# MCU.net
KiCad netlist of a schematic drawn in Altium Designer
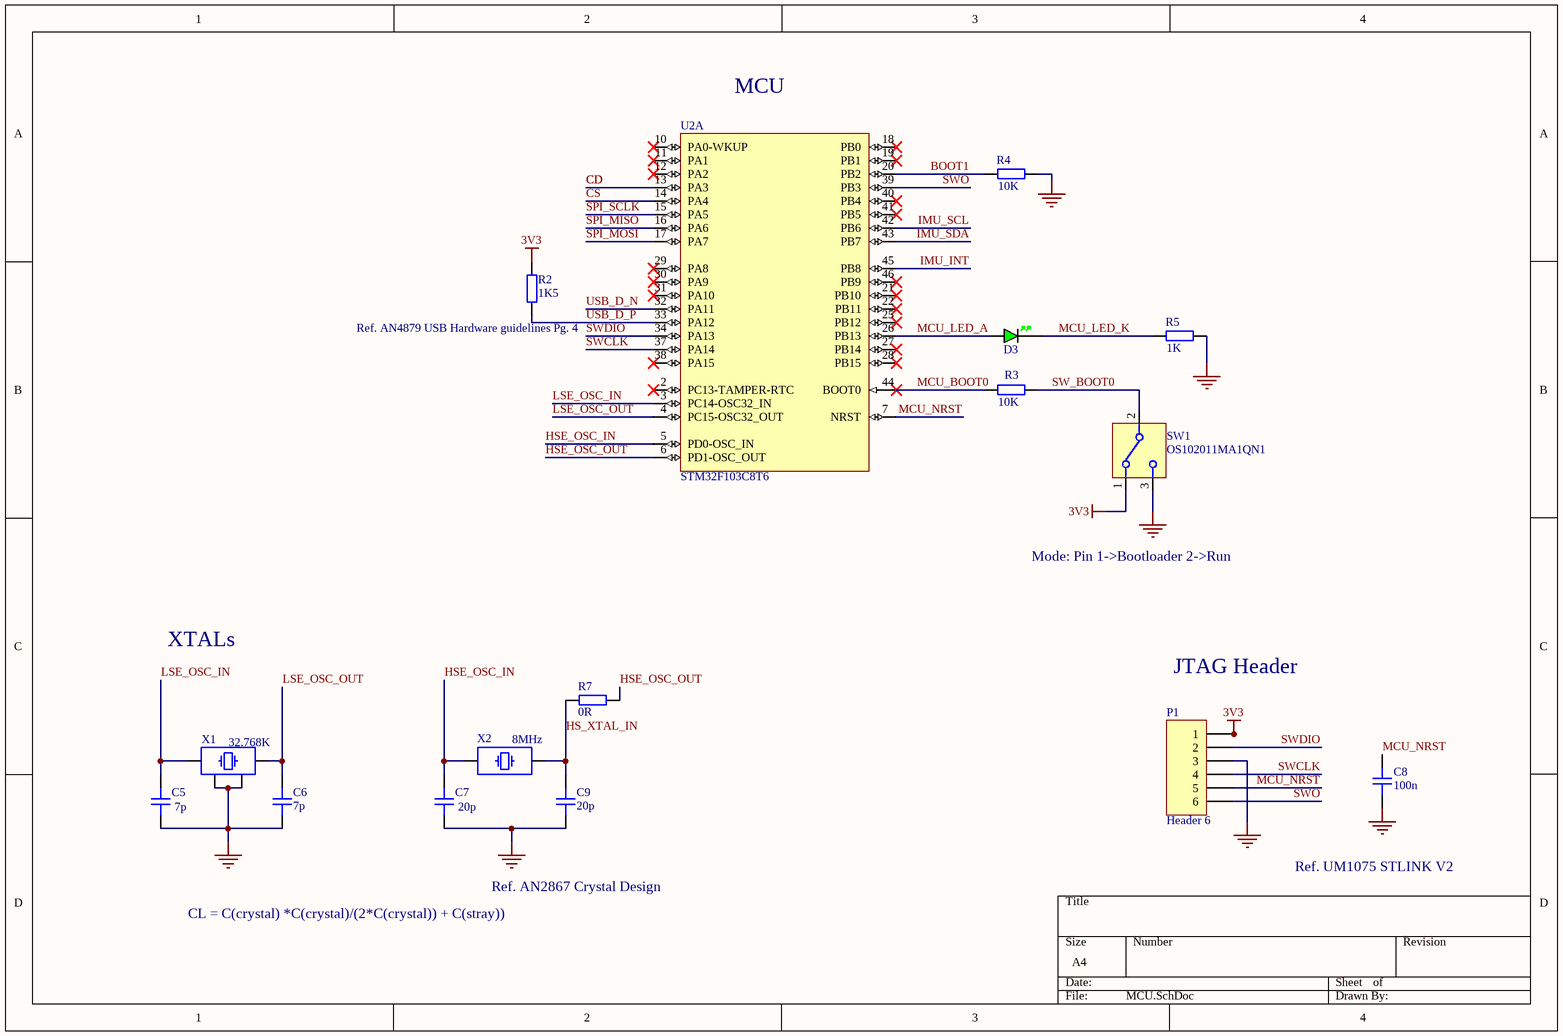
[diagram p0: MCU.SchDoc]

(export (version "E")
  (design (tool "Eeschema 10.0.6"))
  (components
    (comp (ref "C5")
      (value "7p")
      (footprint "CAP_0402")
      (description "Capacitor SMD 0402")
      (libsource (lib "Schematic-Lib-PhilsLab") (part "CAP_0402"))
    )
    (comp (ref "C6")
      (value "7p")
      (footprint "CAP_0402")
      (description "Capacitor SMD 0402")
      (libsource (lib "Schematic-Lib-PhilsLab") (part "CAP_0402"))
    )
    (comp (ref "C7")
      (value "20p")
      (footprint "CAP_0402")
      (description "Capacitor SMD 0402")
      (libsource (lib "Schematic-Lib-PhilsLab") (part "CAP_0402"))
    )
    (comp (ref "C8")
      (value "100n")
      (footprint "CAP_0402")
      (description "Capacitor SMD 0402")
      (libsource (lib "Schematic-Lib-PhilsLab") (part "CAP_0402"))
    )
    (comp (ref "C9")
      (value "20p")
      (footprint "CAP_0402")
      (description "Capacitor SMD 0402")
      (libsource (lib "Schematic-Lib-PhilsLab") (part "CAP_0402"))
    )
    (comp (ref "D3")
      (value "GREEN")
      (footprint "LED_0402_GREEN")
      (description "LED 0402 GREEN SMD")
      (libsource (lib "Schematic-Lib-PhilsLab") (part "LED_0402_GREEN"))
    )
    (comp (ref "P1")
      (value "Header 6")
      (footprint "HDR1X6")
      (description "Header, 6-Pin")
      (fields (field (name "PUBLISHER") "Altium Limited"))
      (libsource (lib "Miscellaneous Connectors") (part "Header 6"))
    )
    (comp (ref "R2")
      (value "1K5")
      (footprint "RES_0402")
      (description "Resistor SMD 0402")
      (libsource (lib "Schematic-Lib-PhilsLab") (part "RES_0402"))
    )
    (comp (ref "R3")
      (value "10K")
      (footprint "RES_0402")
      (description "Resistor SMD 0402")
      (libsource (lib "Schematic-Lib-PhilsLab") (part "RES_0402"))
    )
    (comp (ref "R4")
      (value "10K")
      (footprint "RES_0402")
      (description "Resistor SMD 0402")
      (libsource (lib "Schematic-Lib-PhilsLab") (part "RES_0402"))
    )
    (comp (ref "R5")
      (value "1K")
      (footprint "RES_0402")
      (description "Resistor SMD 0402")
      (libsource (lib "Schematic-Lib-PhilsLab") (part "RES_0402"))
    )
    (comp (ref "R7")
      (value "0R")
      (footprint "RES_0402")
      (description "Resistor SMD 0402")
      (libsource (lib "Schematic-Lib-PhilsLab") (part "RES_0402"))
    )
    (comp (ref "SW1")
      (value "OS102011MA1QN1")
      (footprint "OS102011MA1QN1")
      (description "Slide Switch SPDT Horizontal THT")
      (fields (field (name "MANUFACTURER") "C&K"))
      (libsource (lib "Schematic-Lib-PhilsLab") (part "OS102011MA1QN1"))
    )
    (comp (ref "U2")
      (value "STM32F103C8T6")
      (footprint "STM-LQFP48_L")
      (libsource (lib "Altium Content Vault") (part "MC-ARM-STM32F103X8_B-SQ48"))
    )
    (comp (ref "X1")
      (value "32.768K")
      (footprint "XTAL_2520")
      (description "Crystal SMD 2520")
      (libsource (lib "Schematic-Lib-PhilsLab") (part "XTAL_2520"))
    )
    (comp (ref "X2")
      (value "8MHz")
      (footprint "XTAL_3215-2")
      (description "Crystal SMD 3215")
      (libsource (lib "Schematic-Lib-PhilsLab") (part "XTAL_3215"))
    )
  )
  (nets
    (net (code "1") (name "/BOOT1") (class "Default")
      (node (ref "R4") (pin "2") (pinfunction "2_2") (pintype "passive"))
      (node (ref "U2") (pin "20") (pinfunction "PB2_20") (pintype "bidirectional"))
    )
    (net (code "2") (name "/CD") (class "Default")
      (node (ref "U2") (pin "13") (pinfunction "PA3_13") (pintype "bidirectional"))
    )
    (net (code "3") (name "/CS") (class "Default")
      (node (ref "U2") (pin "14") (pinfunction "PA4_14") (pintype "bidirectional"))
    )
    (net (code "4") (name "/HSE_OSC_IN") (class "Default")
      (node (ref "C7") (pin "2") (pinfunction "2_2") (pintype "passive"))
      (node (ref "U2") (pin "5") (pinfunction "PD0-OSC_IN_5") (pintype "bidirectional"))
      (node (ref "X2") (pin "1") (pinfunction "1_1") (pintype "passive"))
    )
    (net (code "5") (name "/HSE_OSC_OUT") (class "Default")
      (node (ref "R7") (pin "2") (pinfunction "2_2") (pintype "passive"))
      (node (ref "U2") (pin "6") (pinfunction "PD1-OSC_OUT_6") (pintype "bidirectional"))
    )
    (net (code "6") (name "/HS_XTAL_IN") (class "Default")
      (node (ref "C9") (pin "2") (pinfunction "2_2") (pintype "passive"))
      (node (ref "R7") (pin "1") (pinfunction "1_1") (pintype "passive"))
      (node (ref "X2") (pin "2") (pinfunction "2_2") (pintype "passive"))
    )
    (net (code "7") (name "/IMU_INT") (class "Default")
      (node (ref "U2") (pin "45") (pinfunction "PB8_45") (pintype "bidirectional"))
    )
    (net (code "8") (name "/IMU_SCL") (class "Default")
      (node (ref "U2") (pin "42") (pinfunction "PB6_42") (pintype "bidirectional"))
    )
    (net (code "9") (name "/IMU_SDA") (class "Default")
      (node (ref "U2") (pin "43") (pinfunction "PB7_43") (pintype "bidirectional"))
    )
    (net (code "10") (name "/LSE_OSC_IN") (class "Default")
      (node (ref "C5") (pin "2") (pinfunction "2_2") (pintype "passive"))
      (node (ref "U2") (pin "3") (pinfunction "PC14-OSC32_IN_3") (pintype "bidirectional"))
      (node (ref "X1") (pin "1") (pinfunction "1_1") (pintype "passive"))
    )
    (net (code "11") (name "/LSE_OSC_OUT") (class "Default")
      (node (ref "C6") (pin "2") (pinfunction "2_2") (pintype "passive"))
      (node (ref "U2") (pin "4") (pinfunction "PC15-OSC32_OUT_4") (pintype "bidirectional"))
      (node (ref "X1") (pin "3") (pinfunction "3_3") (pintype "passive"))
    )
    (net (code "12") (name "/MCU_BOOT0") (class "Default")
      (node (ref "R3") (pin "2") (pinfunction "2_2") (pintype "passive"))
      (node (ref "U2") (pin "44") (pinfunction "BOOT0_44") (pintype "input"))
    )
    (net (code "13") (name "/MCU_LED_A") (class "Default")
      (node (ref "D3") (pin "A") (pinfunction "A_A") (pintype "passive"))
      (node (ref "U2") (pin "26") (pinfunction "PB13_26") (pintype "bidirectional"))
    )
    (net (code "14") (name "/MCU_LED_K") (class "Default")
      (node (ref "D3") (pin "K") (pinfunction "K_K") (pintype "passive"))
      (node (ref "R5") (pin "2") (pinfunction "2_2") (pintype "passive"))
    )
    (net (code "15") (name "/MCU_NRST") (class "Default")
      (node (ref "C8") (pin "2") (pinfunction "2_2") (pintype "passive"))
      (node (ref "P1") (pin "5") (pinfunction "5_5") (pintype "passive"))
      (node (ref "U2") (pin "7") (pinfunction "NRST_7") (pintype "bidirectional"))
    )
    (net (code "16") (name "/SPI_MISO") (class "Default")
      (node (ref "U2") (pin "16") (pinfunction "PA6_16") (pintype "bidirectional"))
    )
    (net (code "17") (name "/SPI_MOSI") (class "Default")
      (node (ref "U2") (pin "17") (pinfunction "PA7_17") (pintype "bidirectional"))
    )
    (net (code "18") (name "/SPI_SCLK") (class "Default")
      (node (ref "U2") (pin "15") (pinfunction "PA5_15") (pintype "bidirectional"))
    )
    (net (code "19") (name "/SWCLK") (class "Default")
      (node (ref "P1") (pin "4") (pinfunction "4_4") (pintype "passive"))
      (node (ref "U2") (pin "37") (pinfunction "PA14_37") (pintype "bidirectional"))
    )
    (net (code "20") (name "/SWDIO") (class "Default")
      (node (ref "P1") (pin "2") (pinfunction "2_2") (pintype "passive"))
      (node (ref "U2") (pin "34") (pinfunction "PA13_34") (pintype "bidirectional"))
    )
    (net (code "21") (name "/SWO") (class "Default")
      (node (ref "P1") (pin "6") (pinfunction "6_6") (pintype "passive"))
      (node (ref "U2") (pin "39") (pinfunction "PB3_39") (pintype "bidirectional"))
    )
    (net (code "22") (name "/SW_BOOT0") (class "Default")
      (node (ref "R3") (pin "1") (pinfunction "1_1") (pintype "passive"))
      (node (ref "SW1") (pin "2") (pinfunction "COM_2") (pintype "passive"))
    )
    (net (code "23") (name "/USB_D_N") (class "Default")
      (node (ref "U2") (pin "32") (pinfunction "PA11_32") (pintype "bidirectional"))
    )
    (net (code "24") (name "/USB_D_P") (class "Default")
      (node (ref "R2") (pin "2") (pinfunction "2_2") (pintype "passive"))
      (node (ref "U2") (pin "33") (pinfunction "PA12_33") (pintype "bidirectional"))
    )
    (net (code "25") (name "3V3") (class "Default")
      (node (ref "P1") (pin "1") (pinfunction "1_1") (pintype "passive"))
      (node (ref "R2") (pin "1") (pinfunction "1_1") (pintype "passive"))
      (node (ref "SW1") (pin "1") (pinfunction "1_1") (pintype "passive"))
    )
    (net (code "26") (name "GND") (class "Default")
      (node (ref "C5") (pin "1") (pinfunction "1_1") (pintype "passive"))
      (node (ref "C6") (pin "1") (pinfunction "1_1") (pintype "passive"))
      (node (ref "C7") (pin "1") (pinfunction "1_1") (pintype "passive"))
      (node (ref "C8") (pin "1") (pinfunction "1_1") (pintype "passive"))
      (node (ref "C9") (pin "1") (pinfunction "1_1") (pintype "passive"))
      (node (ref "P1") (pin "3") (pinfunction "3_3") (pintype "passive"))
      (node (ref "R4") (pin "1") (pinfunction "1_1") (pintype "passive"))
      (node (ref "R5") (pin "1") (pinfunction "1_1") (pintype "passive"))
      (node (ref "SW1") (pin "3") (pinfunction "3_3") (pintype "passive"))
      (node (ref "X1") (pin "2") (pinfunction "2_2") (pintype "passive"))
      (node (ref "X1") (pin "4") (pinfunction "4_4") (pintype "passive"))
    )
    (net (code "27") (name "unconnected-(U2A-PA0-WKUP-Pad10)") (class "Default")
      (node (ref "U2") (pin "10") (pinfunction "PA0-WKUP_10") (pintype "bidirectional+no_connect"))
    )
    (net (code "28") (name "unconnected-(U2A-PA1-Pad11)") (class "Default")
      (node (ref "U2") (pin "11") (pinfunction "PA1_11") (pintype "bidirectional+no_connect"))
    )
    (net (code "29") (name "unconnected-(U2A-PA2-Pad12)") (class "Default")
      (node (ref "U2") (pin "12") (pinfunction "PA2_12") (pintype "bidirectional+no_connect"))
    )
    (net (code "30") (name "unconnected-(U2A-PA8-Pad29)") (class "Default")
      (node (ref "U2") (pin "29") (pinfunction "PA8_29") (pintype "bidirectional+no_connect"))
    )
    (net (code "31") (name "unconnected-(U2A-PA9-Pad30)") (class "Default")
      (node (ref "U2") (pin "30") (pinfunction "PA9_30") (pintype "bidirectional+no_connect"))
    )
    (net (code "32") (name "unconnected-(U2A-PA10-Pad31)") (class "Default")
      (node (ref "U2") (pin "31") (pinfunction "PA10_31") (pintype "bidirectional+no_connect"))
    )
    (net (code "33") (name "unconnected-(U2A-PA15-Pad38)") (class "Default")
      (node (ref "U2") (pin "38") (pinfunction "PA15_38") (pintype "bidirectional+no_connect"))
    )
    (net (code "34") (name "unconnected-(U2A-PB0-Pad18)") (class "Default")
      (node (ref "U2") (pin "18") (pinfunction "PB0_18") (pintype "bidirectional+no_connect"))
    )
    (net (code "35") (name "unconnected-(U2A-PB1-Pad19)") (class "Default")
      (node (ref "U2") (pin "19") (pinfunction "PB1_19") (pintype "bidirectional+no_connect"))
    )
    (net (code "36") (name "unconnected-(U2A-PB4-Pad40)") (class "Default")
      (node (ref "U2") (pin "40") (pinfunction "PB4_40") (pintype "bidirectional+no_connect"))
    )
    (net (code "37") (name "unconnected-(U2A-PB5-Pad41)") (class "Default")
      (node (ref "U2") (pin "41") (pinfunction "PB5_41") (pintype "bidirectional+no_connect"))
    )
    (net (code "38") (name "unconnected-(U2A-PB9-Pad46)") (class "Default")
      (node (ref "U2") (pin "46") (pinfunction "PB9_46") (pintype "bidirectional+no_connect"))
    )
    (net (code "39") (name "unconnected-(U2A-PB10-Pad21)") (class "Default")
      (node (ref "U2") (pin "21") (pinfunction "PB10_21") (pintype "bidirectional+no_connect"))
    )
    (net (code "40") (name "unconnected-(U2A-PB11-Pad22)") (class "Default")
      (node (ref "U2") (pin "22") (pinfunction "PB11_22") (pintype "bidirectional+no_connect"))
    )
    (net (code "41") (name "unconnected-(U2A-PB12-Pad25)") (class "Default")
      (node (ref "U2") (pin "25") (pinfunction "PB12_25") (pintype "bidirectional+no_connect"))
    )
    (net (code "42") (name "unconnected-(U2A-PB14-Pad27)") (class "Default")
      (node (ref "U2") (pin "27") (pinfunction "PB14_27") (pintype "bidirectional+no_connect"))
    )
    (net (code "43") (name "unconnected-(U2A-PB15-Pad28)") (class "Default")
      (node (ref "U2") (pin "28") (pinfunction "PB15_28") (pintype "bidirectional+no_connect"))
    )
    (net (code "44") (name "unconnected-(U2A-PC13-TAMPER-RTC-Pad2)") (class "Default")
      (node (ref "U2") (pin "2") (pinfunction "PC13-TAMPER-RTC_2") (pintype "bidirectional+no_connect"))
    )
  )
)
